# progr_voltage_src.net
KiCad netlist of a schematic drawn in EAGLE
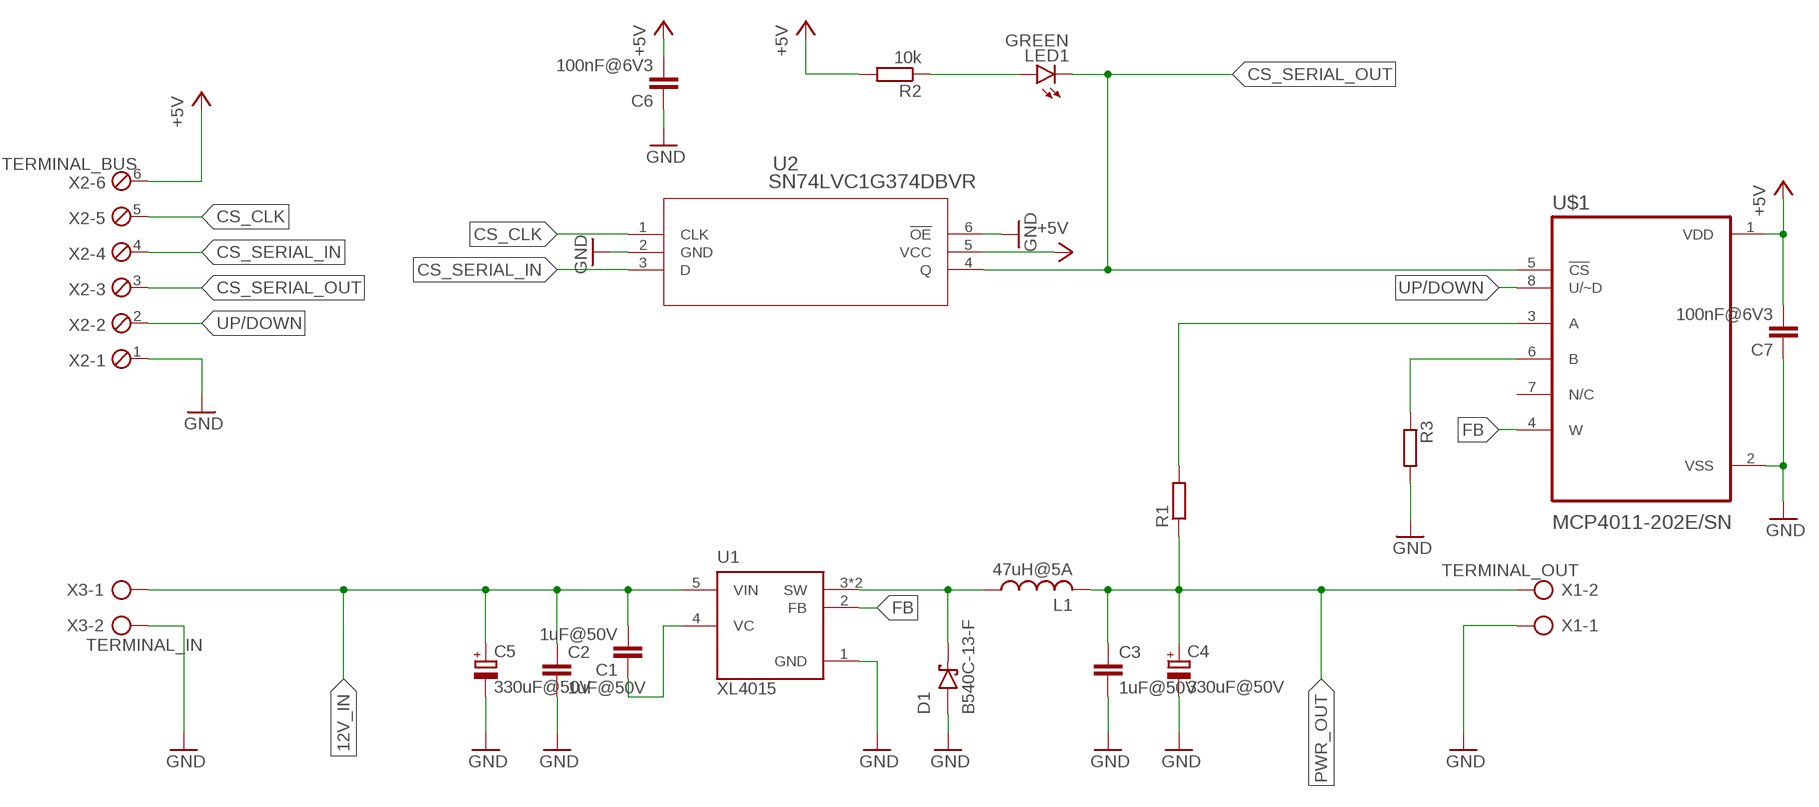
[diagram p0: schematic, sheet 1]

(export (version "E")
  (design (tool "Eeschema 10.0.6"))
  (components
    (comp (ref "C1")
      (value "1uF@50V")
      (footprint "eagle-import:C0603")
      (libsource (lib "eagle-import") (part "C-EUC0603"))
    )
    (comp (ref "C2")
      (value "1uF@50V")
      (footprint "eagle-import:C0603")
      (libsource (lib "eagle-import") (part "C-EUC0603"))
    )
    (comp (ref "C3")
      (value "1uF@50V")
      (footprint "eagle-import:C0603")
      (libsource (lib "eagle-import") (part "C-EUC0603"))
    )
    (comp (ref "C4")
      (value "330uF@50V")
      (footprint "eagle-import:UD-6,3X7,7_NICHICON")
      (libsource (lib "eagle-import") (part "CPOL-EUUD-6,3X7,7"))
    )
    (comp (ref "C5")
      (value "330uF@50V")
      (footprint "eagle-import:UD-6,3X7,7_NICHICON")
      (libsource (lib "eagle-import") (part "CPOL-EUUD-6,3X7,7"))
    )
    (comp (ref "C6")
      (value "100nF@6V3")
      (footprint "eagle-import:C0603")
      (libsource (lib "eagle-import") (part "C-EUC0603"))
    )
    (comp (ref "C7")
      (value "100nF@6V3")
      (footprint "eagle-import:C0603")
      (libsource (lib "eagle-import") (part "C-EUC0603"))
    )
    (comp (ref "D1")
      (value "B540C-13-F")
      (footprint "eagle-import:DIOM6959X245N")
      (fields (field (name "MF") "Diodes Inc."))
      (libsource (lib "eagle-import") (part "B540C-13-F"))
    )
    (comp (ref "L1")
      (value "47uH@5A")
      (footprint "eagle-import:SMD_INDUCTOR_13X12X6")
      (libsource (lib "eagle-import") (part "SMD_INDUCTOR_13X12X6"))
    )
    (comp (ref "LED1")
      (value "GREEN")
      (footprint "eagle-import:LED3MM")
      (libsource (lib "eagle-import") (part "LED3MM"))
    )
    (comp (ref "R1")
      (value "R-EU_R0603")
      (footprint "eagle-import:R0603")
      (libsource (lib "eagle-import") (part "R-EU_R0603"))
    )
    (comp (ref "R2")
      (value "10k")
      (footprint "eagle-import:R0603")
      (libsource (lib "eagle-import") (part "R-EU_R0603"))
    )
    (comp (ref "R3")
      (value "R-EU_R0603")
      (footprint "eagle-import:R0603")
      (libsource (lib "eagle-import") (part "R-EU_R0603"))
    )
    (comp (ref "U$1")
      (value "MCP4011-202E/SN")
      (footprint "eagle-import:SOIC127P600X175-8N")
      (fields (field (name "MF") "Microchip"))
      (libsource (lib "eagle-import") (part "MCP4011-202E/SN"))
    )
    (comp (ref "U1")
      (value "XL4015")
      (footprint "eagle-import:CONV_XL4015")
      (fields (field (name "MF") "XLSEMI"))
      (libsource (lib "eagle-import") (part "XL4015"))
    )
    (comp (ref "U2")
      (value "SN74LVC1G374DBVR")
      (footprint "eagle-import:DBV6")
      (fields (field (name "COPYRIGHT") "Copyright (C) 2023 Ultra Librarian. All rights reserved."))
      (libsource (lib "eagle-import") (part "SN74LVC1G374DBVR"))
    )
    (comp (ref "X1")
      (value "TERMINAL_OUT")
      (footprint "eagle-import:AK500_2")
      (libsource (lib "eagle-import") (part "AK500/2"))
    )
    (comp (ref "X2")
      (value "TERMINAL_BUS")
      (footprint "eagle-import:6POL254")
      (libsource (lib "eagle-import") (part "MPT6"))
    )
    (comp (ref "X3")
      (value "TERMINAL_IN")
      (footprint "eagle-import:AK500_2")
      (libsource (lib "eagle-import") (part "AK500/2"))
    )
  )
  (nets
    (net (code "1") (name "+5V") (class "Default")
      (node (ref "C6") (pin "2") (pinfunction "2_2") (pintype "passive"))
      (node (ref "C7") (pin "2") (pinfunction "2_2") (pintype "passive"))
      (node (ref "R2") (pin "2") (pinfunction "2_2") (pintype "passive"))
      (node (ref "U$1") (pin "1") (pinfunction "VDD_1") (pintype "power_in"))
      (node (ref "U2") (pin "5") (pinfunction "VCC_5") (pintype "power_in"))
      (node (ref "X2") (pin "6") (pinfunction "1_6") (pintype "passive"))
    )
    (net (code "2") (name "12V_IN") (class "Default")
      (node (ref "C1") (pin "2") (pinfunction "2_2") (pintype "passive"))
      (node (ref "C2") (pin "1") (pinfunction "1_1") (pintype "passive"))
      (node (ref "C5") (pin "+") (pinfunction "+_+") (pintype "passive"))
      (node (ref "U1") (pin "5") (pinfunction "VIN_5") (pintype "input"))
      (node (ref "X3") (pin "1") (pinfunction "KL_1") (pintype "passive"))
    )
    (net (code "3") (name "CS_CLK") (class "Default")
      (node (ref "U2") (pin "1") (pinfunction "CLK_1") (pintype "input"))
      (node (ref "X2") (pin "5") (pinfunction "1_5") (pintype "passive"))
    )
    (net (code "4") (name "CS_SERIAL_IN") (class "Default")
      (node (ref "U2") (pin "3") (pinfunction "D_3") (pintype "input"))
      (node (ref "X2") (pin "4") (pinfunction "1_4") (pintype "passive"))
    )
    (net (code "5") (name "CS_SERIAL_OUT") (class "Default")
      (node (ref "LED1") (pin "K") (pinfunction "C_K") (pintype "passive"))
      (node (ref "U$1") (pin "5") (pinfunction "~{CS}_5") (pintype "input"))
      (node (ref "U2") (pin "4") (pinfunction "Q_4") (pintype "output"))
      (node (ref "X2") (pin "3") (pinfunction "1_3") (pintype "passive"))
    )
    (net (code "6") (name "FB") (class "Default")
      (node (ref "U$1") (pin "4") (pinfunction "W_4") (pintype "bidirectional"))
      (node (ref "U1") (pin "2") (pinfunction "FB_2") (pintype "input"))
    )
    (net (code "7") (name "GND") (class "Default")
      (node (ref "C2") (pin "2") (pinfunction "2_2") (pintype "passive"))
      (node (ref "C3") (pin "2") (pinfunction "2_2") (pintype "passive"))
      (node (ref "C4") (pin "-") (pinfunction "-_-") (pintype "passive"))
      (node (ref "C5") (pin "-") (pinfunction "-_-") (pintype "passive"))
      (node (ref "C6") (pin "1") (pinfunction "1_1") (pintype "passive"))
      (node (ref "C7") (pin "1") (pinfunction "1_1") (pintype "passive"))
      (node (ref "D1") (pin "A") (pinfunction "A_A") (pintype "passive"))
      (node (ref "R3") (pin "2") (pinfunction "2_2") (pintype "passive"))
      (node (ref "U$1") (pin "2") (pinfunction "VSS_2") (pintype "power_in"))
      (node (ref "U1") (pin "1") (pinfunction "GND_1") (pintype "power_in"))
      (node (ref "U2") (pin "2") (pinfunction "GND_2") (pintype "power_in"))
      (node (ref "U2") (pin "6") (pinfunction "~{OE}_6") (pintype "input"))
      (node (ref "X1") (pin "1") (pinfunction "KL_1") (pintype "passive"))
      (node (ref "X2") (pin "1") (pinfunction "1_1") (pintype "passive"))
      (node (ref "X3") (pin "2") (pinfunction "KL_2") (pintype "passive"))
    )
    (net (code "8") (name "Net-(D1-K)") (class "Default")
      (node (ref "D1") (pin "C") (pinfunction "K_C") (pintype "passive"))
      (node (ref "L1") (pin "P$1") (pinfunction "1_P$1") (pintype "passive"))
      (node (ref "U1") (pin "3") (pinfunction "SW_3") (pintype "output"))
      (node (ref "U1") (pin "3.1") (pinfunction "SW_3.1") (pintype "output"))
    )
    (net (code "9") (name "Net-(LED1-PadA)") (class "Default")
      (node (ref "LED1") (pin "A") (pinfunction "A_A") (pintype "passive"))
      (node (ref "R2") (pin "1") (pinfunction "1_1") (pintype "passive"))
    )
    (net (code "10") (name "Net-(U$1-A)") (class "Default")
      (node (ref "R1") (pin "2") (pinfunction "2_2") (pintype "passive"))
      (node (ref "U$1") (pin "3") (pinfunction "A_3") (pintype "bidirectional"))
    )
    (net (code "11") (name "Net-(U$1-B)") (class "Default")
      (node (ref "R3") (pin "1") (pinfunction "1_1") (pintype "passive"))
      (node (ref "U$1") (pin "6") (pinfunction "B_6") (pintype "bidirectional"))
    )
    (net (code "12") (name "Net-(U1-VC)") (class "Default")
      (node (ref "C1") (pin "1") (pinfunction "1_1") (pintype "passive"))
      (node (ref "U1") (pin "4") (pinfunction "VC_4") (pintype "passive"))
    )
    (net (code "13") (name "PWR_OUT") (class "Default")
      (node (ref "C3") (pin "1") (pinfunction "1_1") (pintype "passive"))
      (node (ref "C4") (pin "+") (pinfunction "+_+") (pintype "passive"))
      (node (ref "L1") (pin "P$2") (pinfunction "2_P$2") (pintype "passive"))
      (node (ref "R1") (pin "1") (pinfunction "1_1") (pintype "passive"))
      (node (ref "X1") (pin "2") (pinfunction "KL_2") (pintype "passive"))
    )
    (net (code "14") (name "UP{slash}DOWN") (class "Default")
      (node (ref "U$1") (pin "8") (pinfunction "U/~{D}_8") (pintype "input"))
      (node (ref "X2") (pin "2") (pinfunction "1_2") (pintype "passive"))
    )
    (net (code "15") (name "unconnected-(U$1-N{slash}C-Pad7)") (class "Default")
      (node (ref "U$1") (pin "7") (pinfunction "N/C_7") (pintype "bidirectional"))
    )
  )
)
